# RF.net
KiCad netlist of a schematic drawn in Altium Designer
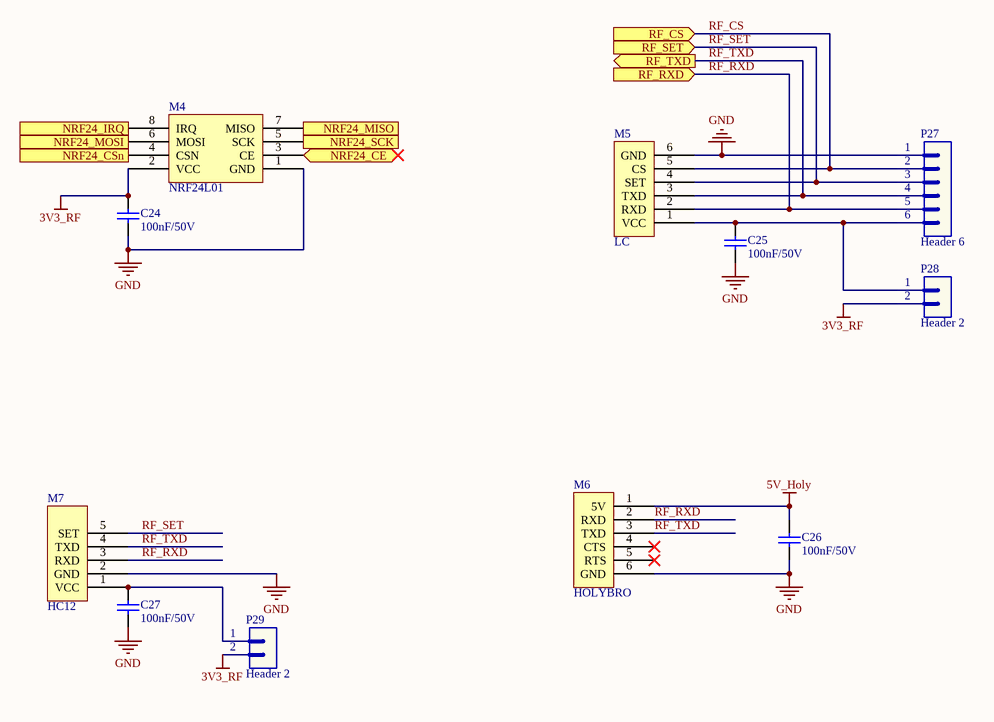
[diagram p0: RF.SchDoc]

(export (version "E")
  (design (tool "Eeschema 10.0.6"))
  (components
    (comp (ref "C24")
      (value "100nF/50V")
      (footprint "CAP-SM-0805")
      (description "CAP CER 0.1UF 50V Y5V 0805")
      (fields
        (field (name "MANUFACTURER") "Samsung Electro-Mechanics")
        (field (name "MANUFACTURER PART NUMBER") "CL21F104ZBCNNNC")
      )
      (libsource (lib "Capacitor") (part "Cap-100nF-50V-0805"))
    )
    (comp (ref "C25")
      (value "100nF/50V")
      (footprint "CAP-SM-0805")
      (description "CAP CER 0.1UF 50V Y5V 0805")
      (fields
        (field (name "MANUFACTURER") "Samsung Electro-Mechanics")
        (field (name "MANUFACTURER PART NUMBER") "CL21F104ZBCNNNC")
      )
      (libsource (lib "Capacitor") (part "Cap-100nF-50V-0805"))
    )
    (comp (ref "C26")
      (value "100nF/50V")
      (footprint "CAP-SM-0805")
      (description "CAP CER 0.1UF 50V Y5V 0805")
      (fields
        (field (name "MANUFACTURER") "Samsung Electro-Mechanics")
        (field (name "MANUFACTURER PART NUMBER") "CL21F104ZBCNNNC")
      )
      (libsource (lib "Capacitor") (part "Cap-100nF-50V-0805"))
    )
    (comp (ref "C27")
      (value "100nF/50V")
      (footprint "CAP-SM-0805")
      (description "CAP CER 0.1UF 50V Y5V 0805")
      (fields
        (field (name "MANUFACTURER") "Samsung Electro-Mechanics")
        (field (name "MANUFACTURER PART NUMBER") "CL21F104ZBCNNNC")
      )
      (libsource (lib "Capacitor") (part "Cap-100nF-50V-0805"))
    )
    (comp (ref "M4") (value "NRF24L01") (footprint "NRF24L01") (libsource (lib "chicken") (part "NRF24L01")))
    (comp (ref "M5") (value "LC") (footprint "LC12S") (libsource (lib "chicken") (part "LC12S")))
    (comp (ref "M6") (value "HOLYBRO") (footprint "HOLYBRO") (libsource (lib "chicken") (part "HOLYBRO")))
    (comp (ref "M7") (value "HC12") (footprint "HC12") (libsource (lib "chicken") (part "HC12")))
    (comp (ref "P27")
      (value "Header 6")
      (footprint "JP6")
      (description "Header, 6-Pin")
      (fields (field (name "PUBLISHER") "Altium Limited"))
      (libsource (lib "Header-connector") (part "Header 6"))
    )
    (comp (ref "P28")
      (value "Header 2")
      (footprint "JP2")
      (description "Header, 2-Pin")
      (fields (field (name "PUBLISHER") "Altium Limited"))
      (libsource (lib "Header-connector") (part "Header 2"))
    )
    (comp (ref "P29")
      (value "Header 2")
      (footprint "JP2")
      (description "Header, 2-Pin")
      (fields (field (name "PUBLISHER") "Altium Limited"))
      (libsource (lib "Header-connector") (part "Header 2"))
    )
  )
  (nets
    (net (code "1") (name "/NRF24_CE") (class "Default")
      (node (ref "M4") (pin "3") (pinfunction "CE_3") (pintype "passive"))
    )
    (net (code "2") (name "/NRF24_CSn") (class "Default")
      (node (ref "M4") (pin "4") (pinfunction "CSN_4") (pintype "passive"))
    )
    (net (code "3") (name "/NRF24_IRQ") (class "Default")
      (node (ref "M4") (pin "8") (pinfunction "IRQ_8") (pintype "passive"))
    )
    (net (code "4") (name "/NRF24_MISO") (class "Default")
      (node (ref "M4") (pin "7") (pinfunction "MISO_7") (pintype "passive"))
    )
    (net (code "5") (name "/NRF24_MOSI") (class "Default")
      (node (ref "M4") (pin "6") (pinfunction "MOSI_6") (pintype "passive"))
    )
    (net (code "6") (name "/NRF24_SCK") (class "Default")
      (node (ref "M4") (pin "5") (pinfunction "SCK_5") (pintype "passive"))
    )
    (net (code "7") (name "/RF_CS") (class "Default")
      (node (ref "M5") (pin "5") (pinfunction "CS_5") (pintype "passive"))
      (node (ref "P27") (pin "2") (pinfunction "2_2") (pintype "passive"))
    )
    (net (code "8") (name "/RF_RXD") (class "Default")
      (node (ref "M5") (pin "2") (pinfunction "RXD_2") (pintype "passive"))
      (node (ref "M6") (pin "2") (pinfunction "RXD_2") (pintype "passive"))
      (node (ref "M7") (pin "3") (pinfunction "RXD_3") (pintype "passive"))
      (node (ref "P27") (pin "5") (pinfunction "5_5") (pintype "passive"))
    )
    (net (code "9") (name "/RF_SET") (class "Default")
      (node (ref "M5") (pin "4") (pinfunction "SET_4") (pintype "passive"))
      (node (ref "M7") (pin "5") (pinfunction "SET_5") (pintype "passive"))
      (node (ref "P27") (pin "3") (pinfunction "3_3") (pintype "passive"))
    )
    (net (code "10") (name "/RF_TXD") (class "Default")
      (node (ref "M5") (pin "3") (pinfunction "TXD_3") (pintype "passive"))
      (node (ref "M6") (pin "3") (pinfunction "TXD_3") (pintype "passive"))
      (node (ref "M7") (pin "4") (pinfunction "TXD_4") (pintype "passive"))
      (node (ref "P27") (pin "4") (pinfunction "4_4") (pintype "passive"))
    )
    (net (code "11") (name "3V3_RF") (class "Default")
      (node (ref "C24") (pin "2") (pinfunction "2_2") (pintype "passive"))
      (node (ref "M4") (pin "2") (pinfunction "VCC_2") (pintype "passive"))
      (node (ref "P28") (pin "2") (pinfunction "2_2") (pintype "passive"))
      (node (ref "P29") (pin "2") (pinfunction "2_2") (pintype "passive"))
    )
    (net (code "12") (name "5V_Holy") (class "Default")
      (node (ref "C26") (pin "2") (pinfunction "2_2") (pintype "passive"))
      (node (ref "M6") (pin "1") (pinfunction "5V_1") (pintype "passive"))
    )
    (net (code "13") (name "GND") (class "Default")
      (node (ref "C24") (pin "1") (pinfunction "1_1") (pintype "passive"))
      (node (ref "C25") (pin "1") (pinfunction "1_1") (pintype "passive"))
      (node (ref "C26") (pin "1") (pinfunction "1_1") (pintype "passive"))
      (node (ref "C27") (pin "1") (pinfunction "1_1") (pintype "passive"))
      (node (ref "M4") (pin "1") (pinfunction "GND_1") (pintype "passive"))
      (node (ref "M5") (pin "6") (pinfunction "GND_6") (pintype "passive"))
      (node (ref "M6") (pin "6") (pinfunction "GND_6") (pintype "passive"))
      (node (ref "M7") (pin "2") (pinfunction "GND_2") (pintype "passive"))
      (node (ref "P27") (pin "1") (pinfunction "1_1") (pintype "passive"))
    )
    (net (code "14") (name "Net-(M5-VCC)") (class "Default")
      (node (ref "C25") (pin "2") (pinfunction "2_2") (pintype "passive"))
      (node (ref "M5") (pin "1") (pinfunction "VCC_1") (pintype "passive"))
      (node (ref "P27") (pin "6") (pinfunction "6_6") (pintype "passive"))
      (node (ref "P28") (pin "1") (pinfunction "1_1") (pintype "passive"))
    )
    (net (code "15") (name "Net-(M7-VCC)") (class "Default")
      (node (ref "C27") (pin "2") (pinfunction "2_2") (pintype "passive"))
      (node (ref "M7") (pin "1") (pinfunction "VCC_1") (pintype "passive"))
      (node (ref "P29") (pin "1") (pinfunction "1_1") (pintype "passive"))
    )
    (net (code "16") (name "unconnected-(M6-CTS-Pad4)") (class "Default")
      (node (ref "M6") (pin "4") (pinfunction "CTS_4") (pintype "passive+no_connect"))
    )
    (net (code "17") (name "unconnected-(M6-RTS-Pad5)") (class "Default")
      (node (ref "M6") (pin "5") (pinfunction "RTS_5") (pintype "passive+no_connect"))
    )
  )
)
